# driver_and_mosfets.net
KiCad netlist of a schematic drawn in Altium Designer
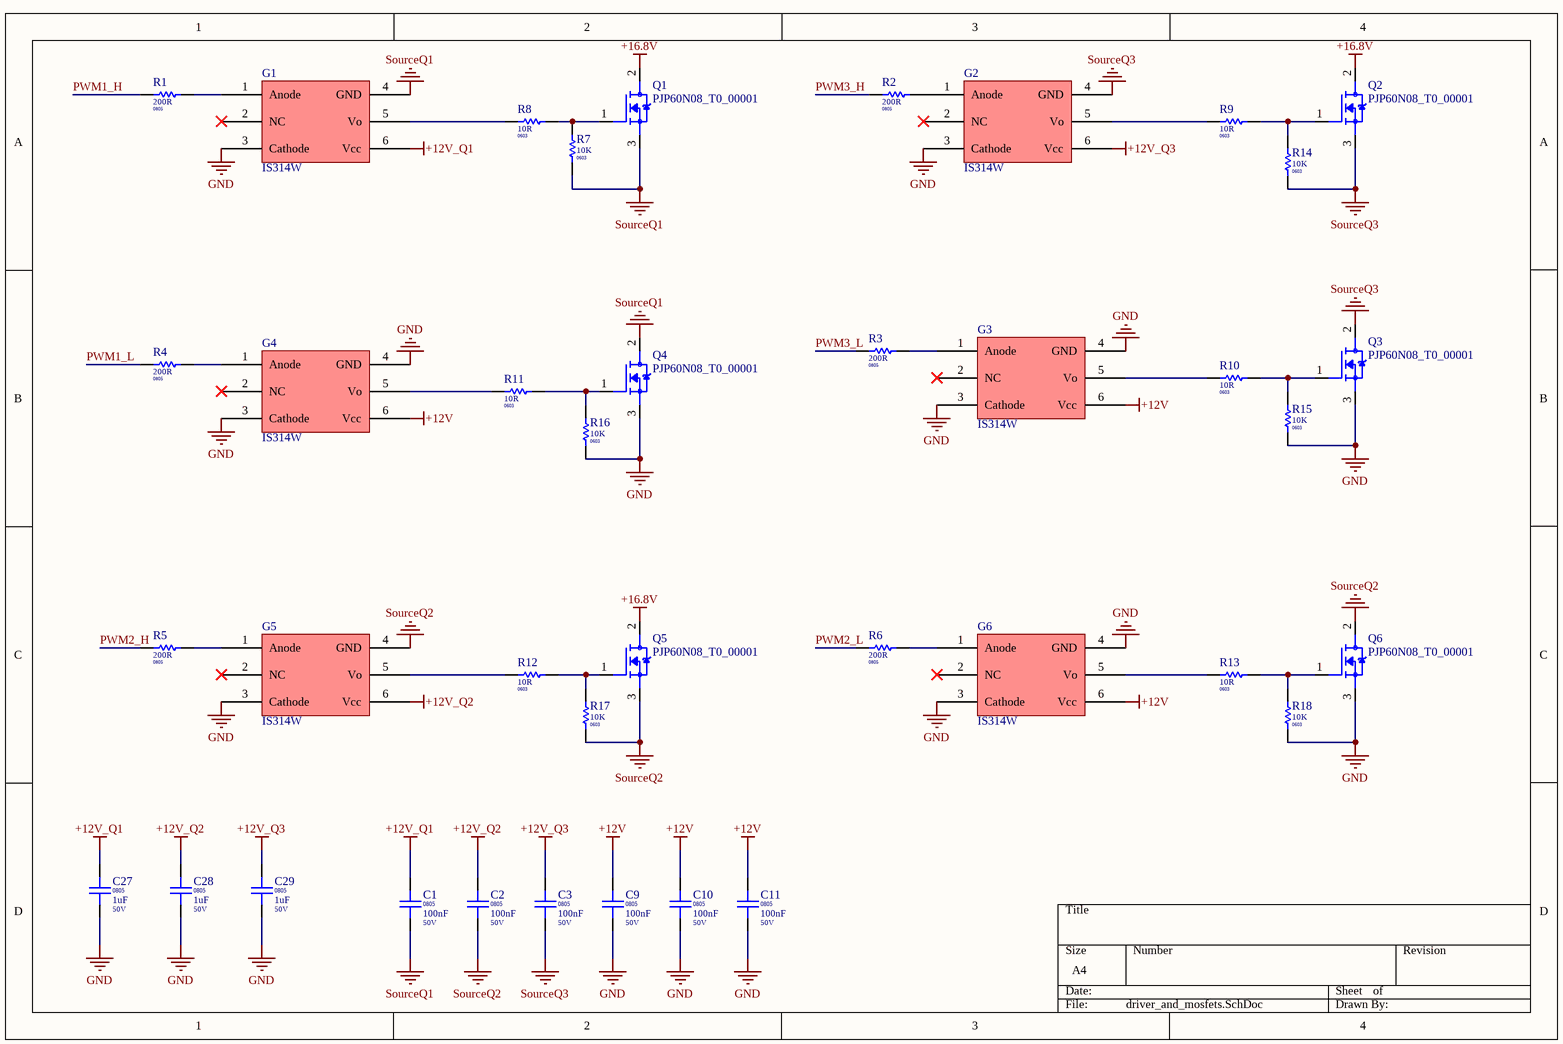
[diagram p0: driver_and_mosfets.SchDoc]

(export (version "E")
  (design (tool "Eeschema 10.0.6"))
  (components
    (comp (ref "C1")
      (value "100nF")
      (footprint "CAPC 0805")
      (description "Capacitor Ceramic 100nF 50V 0805")
      (fields
        (field (name "TOLERANCE") "%10")
        (field (name "PACKAGE / CASE") "0805")
        (field (name "VOLTAGE") "50V")
        (field (name "PART NUMBER") "CAPC0572")
      )
      (libsource (lib "AESK Database Library") (part "NPCapacitor"))
    )
    (comp (ref "C2")
      (value "100nF")
      (footprint "CAPC 0805")
      (description "Capacitor Ceramic 100nF 50V 0805")
      (fields
        (field (name "TOLERANCE") "%10")
        (field (name "PACKAGE / CASE") "0805")
        (field (name "VOLTAGE") "50V")
        (field (name "PART NUMBER") "CAPC0572")
      )
      (libsource (lib "AESK Database Library") (part "NPCapacitor"))
    )
    (comp (ref "C3")
      (value "100nF")
      (footprint "CAPC 0805")
      (description "Capacitor Ceramic 100nF 50V 0805")
      (fields
        (field (name "TOLERANCE") "%10")
        (field (name "PACKAGE / CASE") "0805")
        (field (name "VOLTAGE") "50V")
        (field (name "PART NUMBER") "CAPC0572")
      )
      (libsource (lib "AESK Database Library") (part "NPCapacitor"))
    )
    (comp (ref "C9")
      (value "100nF")
      (footprint "CAPC 0805")
      (description "Capacitor Ceramic 100nF 50V 0805")
      (fields
        (field (name "TOLERANCE") "%10")
        (field (name "PACKAGE / CASE") "0805")
        (field (name "VOLTAGE") "50V")
        (field (name "PART NUMBER") "CAPC0572")
      )
      (libsource (lib "AESK Database Library") (part "NPCapacitor"))
    )
    (comp (ref "C10")
      (value "100nF")
      (footprint "CAPC 0805")
      (description "Capacitor Ceramic 100nF 50V 0805")
      (fields
        (field (name "TOLERANCE") "%10")
        (field (name "PACKAGE / CASE") "0805")
        (field (name "VOLTAGE") "50V")
        (field (name "PART NUMBER") "CAPC0572")
      )
      (libsource (lib "AESK Database Library") (part "NPCapacitor"))
    )
    (comp (ref "C11")
      (value "100nF")
      (footprint "CAPC 0805")
      (description "Capacitor Ceramic 100nF 50V 0805")
      (fields
        (field (name "TOLERANCE") "%10")
        (field (name "PACKAGE / CASE") "0805")
        (field (name "VOLTAGE") "50V")
        (field (name "PART NUMBER") "CAPC0572")
      )
      (libsource (lib "AESK Database Library") (part "NPCapacitor"))
    )
    (comp (ref "C27")
      (value "1uF")
      (footprint "CAPC 0805")
      (description "Capacitor Ceramic 1uF 50V 0805")
      (fields
        (field (name "TOLERANCE") "%10")
        (field (name "PACKAGE / CASE") "0805")
        (field (name "VOLTAGE") "50V")
        (field (name "PART NUMBER") "CAPC0580")
      )
      (libsource (lib "AESK Database Library") (part "NPCapacitor"))
    )
    (comp (ref "C28")
      (value "1uF")
      (footprint "CAPC 0805")
      (description "Capacitor Ceramic 1uF 50V 0805")
      (fields
        (field (name "TOLERANCE") "%10")
        (field (name "PACKAGE / CASE") "0805")
        (field (name "VOLTAGE") "50V")
        (field (name "PART NUMBER") "CAPC0580")
      )
      (libsource (lib "AESK Database Library") (part "NPCapacitor"))
    )
    (comp (ref "C29")
      (value "1uF")
      (footprint "CAPC 0805")
      (description "Capacitor Ceramic 1uF 50V 0805")
      (fields
        (field (name "TOLERANCE") "%10")
        (field (name "PACKAGE / CASE") "0805")
        (field (name "VOLTAGE") "50V")
        (field (name "PART NUMBER") "CAPC0580")
      )
      (libsource (lib "AESK Database Library") (part "NPCapacitor"))
    )
    (comp (ref "G1")
      (value "IS314W")
      (footprint "SOIC127P1150X360-6N")
      (description "IC-314 OPTO GATE DRVR 5KV SO6 STRETCHED")
      (libsource (lib "ESC") (part "IS314W"))
    )
    (comp (ref "G2")
      (value "IS314W")
      (footprint "SOIC127P1150X360-6N")
      (description "IC-314 OPTO GATE DRVR 5KV SO6 STRETCHED")
      (libsource (lib "ESC") (part "IS314W"))
    )
    (comp (ref "G3")
      (value "IS314W")
      (footprint "SOIC127P1150X360-6N")
      (description "IC-314 OPTO GATE DRVR 5KV SO6 STRETCHED")
      (libsource (lib "ESC") (part "IS314W"))
    )
    (comp (ref "G4")
      (value "IS314W")
      (footprint "SOIC127P1150X360-6N")
      (description "IC-314 OPTO GATE DRVR 5KV SO6 STRETCHED")
      (libsource (lib "ESC") (part "IS314W"))
    )
    (comp (ref "G5")
      (value "IS314W")
      (footprint "SOIC127P1150X360-6N")
      (description "IC-314 OPTO GATE DRVR 5KV SO6 STRETCHED")
      (libsource (lib "ESC") (part "IS314W"))
    )
    (comp (ref "G6")
      (value "IS314W")
      (footprint "SOIC127P1150X360-6N")
      (description "IC-314 OPTO GATE DRVR 5KV SO6 STRETCHED")
      (libsource (lib "ESC") (part "IS314W"))
    )
    (comp (ref "Q1")
      (value "PJP60N08_T0_00001")
      (footprint "TO-220-3")
      (description "MOSFET DIS.60A 80V N-CH TO220AB SWITCH THT")
      (fields (field (name "MP") "IRF520NPBF") (field (name "MF") "Infineon Technologies"))
      (libsource (lib "ESC") (part "PJP60N08_T0_00001"))
    )
    (comp (ref "Q2")
      (value "PJP60N08_T0_00001")
      (footprint "TO-220-3")
      (description "MOSFET DIS.60A 80V N-CH TO220AB SWITCH THT")
      (fields (field (name "MP") "IRF520NPBF") (field (name "MF") "Infineon Technologies"))
      (libsource (lib "ESC") (part "PJP60N08_T0_00001"))
    )
    (comp (ref "Q3")
      (value "PJP60N08_T0_00001")
      (footprint "TO-220-3")
      (description "MOSFET DIS.60A 80V N-CH TO220AB SWITCH THT")
      (fields (field (name "MP") "IRF520NPBF") (field (name "MF") "Infineon Technologies"))
      (libsource (lib "ESC") (part "PJP60N08_T0_00001"))
    )
    (comp (ref "Q4")
      (value "PJP60N08_T0_00001")
      (footprint "TO-220-3")
      (description "MOSFET DIS.60A 80V N-CH TO220AB SWITCH THT")
      (fields (field (name "MP") "IRF520NPBF") (field (name "MF") "Infineon Technologies"))
      (libsource (lib "ESC") (part "PJP60N08_T0_00001"))
    )
    (comp (ref "Q5")
      (value "PJP60N08_T0_00001")
      (footprint "TO-220-3")
      (description "MOSFET DIS.60A 80V N-CH TO220AB SWITCH THT")
      (fields (field (name "MP") "IRF520NPBF") (field (name "MF") "Infineon Technologies"))
      (libsource (lib "ESC") (part "PJP60N08_T0_00001"))
    )
    (comp (ref "Q6")
      (value "PJP60N08_T0_00001")
      (footprint "TO-220-3")
      (description "MOSFET DIS.60A 80V N-CH TO220AB SWITCH THT")
      (fields (field (name "MP") "IRF520NPBF") (field (name "MF") "Infineon Technologies"))
      (libsource (lib "ESC") (part "PJP60N08_T0_00001"))
    )
    (comp (ref "R1")
      (value "200R")
      (footprint "RESC 0805")
      (description "200R 0805")
      (fields
        (field (name "TOLERANCE") "%5")
        (field (name "POWER") "1/10W")
        (field (name "PACKAGE / CASE") "0805")
      )
      (libsource (lib "AESK Database Library") (part "Resistor"))
    )
    (comp (ref "R2")
      (value "200R")
      (footprint "RESC 0805")
      (description "200R 0805")
      (fields
        (field (name "TOLERANCE") "%5")
        (field (name "POWER") "1/10W")
        (field (name "PACKAGE / CASE") "0805")
      )
      (libsource (lib "AESK Database Library") (part "Resistor"))
    )
    (comp (ref "R3")
      (value "200R")
      (footprint "RESC 0805")
      (description "200R 0805")
      (fields
        (field (name "TOLERANCE") "%5")
        (field (name "POWER") "1/10W")
        (field (name "PACKAGE / CASE") "0805")
      )
      (libsource (lib "AESK Database Library") (part "Resistor"))
    )
    (comp (ref "R4")
      (value "200R")
      (footprint "RESC 0805")
      (description "200R 0805")
      (fields
        (field (name "TOLERANCE") "%5")
        (field (name "POWER") "1/10W")
        (field (name "PACKAGE / CASE") "0805")
      )
      (libsource (lib "AESK Database Library") (part "Resistor"))
    )
    (comp (ref "R5")
      (value "200R")
      (footprint "RESC 0805")
      (description "200R 0805")
      (fields
        (field (name "TOLERANCE") "%5")
        (field (name "POWER") "1/10W")
        (field (name "PACKAGE / CASE") "0805")
      )
      (libsource (lib "AESK Database Library") (part "Resistor"))
    )
    (comp (ref "R6")
      (value "200R")
      (footprint "RESC 0805")
      (description "200R 0805")
      (fields
        (field (name "TOLERANCE") "%5")
        (field (name "POWER") "1/10W")
        (field (name "PACKAGE / CASE") "0805")
      )
      (libsource (lib "AESK Database Library") (part "Resistor"))
    )
    (comp (ref "R7")
      (value "10K")
      (footprint "RESC 0603")
      (description "10K 0603")
      (fields
        (field (name "TOLERANCE") "%5")
        (field (name "POWER") "1/10W")
        (field (name "PACKAGE / CASE") "0603")
      )
      (libsource (lib "AESK Database Library") (part "Resistor"))
    )
    (comp (ref "R8")
      (value "10R")
      (footprint "RESC 0603")
      (description "10R 0603")
      (fields
        (field (name "TOLERANCE") "%5")
        (field (name "POWER") "1/10W")
        (field (name "PACKAGE / CASE") "0603")
      )
      (libsource (lib "AESK Database Library") (part "Resistor"))
    )
    (comp (ref "R9")
      (value "10R")
      (footprint "RESC 0603")
      (description "10R 0603")
      (fields
        (field (name "TOLERANCE") "%5")
        (field (name "POWER") "1/10W")
        (field (name "PACKAGE / CASE") "0603")
      )
      (libsource (lib "AESK Database Library") (part "Resistor"))
    )
    (comp (ref "R10")
      (value "10R")
      (footprint "RESC 0603")
      (description "10R 0603")
      (fields
        (field (name "TOLERANCE") "%5")
        (field (name "POWER") "1/10W")
        (field (name "PACKAGE / CASE") "0603")
      )
      (libsource (lib "AESK Database Library") (part "Resistor"))
    )
    (comp (ref "R11")
      (value "10R")
      (footprint "RESC 0603")
      (description "10R 0603")
      (fields
        (field (name "TOLERANCE") "%5")
        (field (name "POWER") "1/10W")
        (field (name "PACKAGE / CASE") "0603")
      )
      (libsource (lib "AESK Database Library") (part "Resistor"))
    )
    (comp (ref "R12")
      (value "10R")
      (footprint "RESC 0603")
      (description "10R 0603")
      (fields
        (field (name "TOLERANCE") "%5")
        (field (name "POWER") "1/10W")
        (field (name "PACKAGE / CASE") "0603")
      )
      (libsource (lib "AESK Database Library") (part "Resistor"))
    )
    (comp (ref "R13")
      (value "10R")
      (footprint "RESC 0603")
      (description "10R 0603")
      (fields
        (field (name "TOLERANCE") "%5")
        (field (name "POWER") "1/10W")
        (field (name "PACKAGE / CASE") "0603")
      )
      (libsource (lib "AESK Database Library") (part "Resistor"))
    )
    (comp (ref "R14")
      (value "10K")
      (footprint "RESC 0603")
      (description "10K 0603")
      (fields
        (field (name "TOLERANCE") "%5")
        (field (name "POWER") "1/10W")
        (field (name "PACKAGE / CASE") "0603")
      )
      (libsource (lib "AESK Database Library") (part "Resistor"))
    )
    (comp (ref "R15")
      (value "10K")
      (footprint "RESC 0603")
      (description "10K 0603")
      (fields
        (field (name "TOLERANCE") "%5")
        (field (name "POWER") "1/10W")
        (field (name "PACKAGE / CASE") "0603")
      )
      (libsource (lib "AESK Database Library") (part "Resistor"))
    )
    (comp (ref "R16")
      (value "10K")
      (footprint "RESC 0603")
      (description "10K 0603")
      (fields
        (field (name "TOLERANCE") "%5")
        (field (name "POWER") "1/10W")
        (field (name "PACKAGE / CASE") "0603")
      )
      (libsource (lib "AESK Database Library") (part "Resistor"))
    )
    (comp (ref "R17")
      (value "10K")
      (footprint "RESC 0603")
      (description "10K 0603")
      (fields
        (field (name "TOLERANCE") "%5")
        (field (name "POWER") "1/10W")
        (field (name "PACKAGE / CASE") "0603")
      )
      (libsource (lib "AESK Database Library") (part "Resistor"))
    )
    (comp (ref "R18")
      (value "10K")
      (footprint "RESC 0603")
      (description "10K 0603")
      (fields
        (field (name "TOLERANCE") "%5")
        (field (name "POWER") "1/10W")
        (field (name "PACKAGE / CASE") "0603")
      )
      (libsource (lib "AESK Database Library") (part "Resistor"))
    )
  )
  (nets
    (net (code "1") (name "+12V") (class "Default")
      (node (ref "C10") (pin "2") (pinfunction "2_2") (pintype "passive"))
      (node (ref "C11") (pin "2") (pinfunction "2_2") (pintype "passive"))
      (node (ref "C9") (pin "2") (pinfunction "2_2") (pintype "passive"))
      (node (ref "G3") (pin "6") (pinfunction "Vcc_6") (pintype "passive"))
      (node (ref "G4") (pin "6") (pinfunction "Vcc_6") (pintype "passive"))
      (node (ref "G6") (pin "6") (pinfunction "Vcc_6") (pintype "passive"))
    )
    (net (code "2") (name "+12V_Q1") (class "Default")
      (node (ref "C1") (pin "2") (pinfunction "2_2") (pintype "passive"))
      (node (ref "C27") (pin "2") (pinfunction "2_2") (pintype "passive"))
      (node (ref "G1") (pin "6") (pinfunction "Vcc_6") (pintype "passive"))
    )
    (net (code "3") (name "+12V_Q2") (class "Default")
      (node (ref "C2") (pin "2") (pinfunction "2_2") (pintype "passive"))
      (node (ref "C28") (pin "2") (pinfunction "2_2") (pintype "passive"))
      (node (ref "G5") (pin "6") (pinfunction "Vcc_6") (pintype "passive"))
    )
    (net (code "4") (name "+12V_Q3") (class "Default")
      (node (ref "C29") (pin "2") (pinfunction "2_2") (pintype "passive"))
      (node (ref "C3") (pin "2") (pinfunction "2_2") (pintype "passive"))
      (node (ref "G2") (pin "6") (pinfunction "Vcc_6") (pintype "passive"))
    )
    (net (code "5") (name "+16.8V") (class "Default")
      (node (ref "Q1") (pin "2") (pinfunction "D_2") (pintype "passive"))
      (node (ref "Q2") (pin "2") (pinfunction "D_2") (pintype "passive"))
      (node (ref "Q5") (pin "2") (pinfunction "D_2") (pintype "passive"))
    )
    (net (code "6") (name "/PWM1_H") (class "Default")
      (node (ref "R1") (pin "1") (pinfunction "1_1") (pintype "passive"))
    )
    (net (code "7") (name "/PWM1_L") (class "Default")
      (node (ref "R4") (pin "1") (pinfunction "1_1") (pintype "passive"))
    )
    (net (code "8") (name "/PWM2_H") (class "Default")
      (node (ref "R5") (pin "1") (pinfunction "1_1") (pintype "passive"))
    )
    (net (code "9") (name "/PWM2_L") (class "Default")
      (node (ref "R6") (pin "1") (pinfunction "1_1") (pintype "passive"))
    )
    (net (code "10") (name "/PWM3_H") (class "Default")
      (node (ref "R2") (pin "1") (pinfunction "1_1") (pintype "passive"))
    )
    (net (code "11") (name "/PWM3_L") (class "Default")
      (node (ref "R3") (pin "1") (pinfunction "1_1") (pintype "passive"))
    )
    (net (code "12") (name "GND") (class "Default")
      (node (ref "C10") (pin "1") (pinfunction "1_1") (pintype "passive"))
      (node (ref "C11") (pin "1") (pinfunction "1_1") (pintype "passive"))
      (node (ref "C27") (pin "1") (pinfunction "1_1") (pintype "passive"))
      (node (ref "C28") (pin "1") (pinfunction "1_1") (pintype "passive"))
      (node (ref "C29") (pin "1") (pinfunction "1_1") (pintype "passive"))
      (node (ref "C9") (pin "1") (pinfunction "1_1") (pintype "passive"))
      (node (ref "G1") (pin "3") (pinfunction "Cathode_3") (pintype "passive"))
      (node (ref "G2") (pin "3") (pinfunction "Cathode_3") (pintype "passive"))
      (node (ref "G3") (pin "3") (pinfunction "Cathode_3") (pintype "passive"))
      (node (ref "G3") (pin "4") (pinfunction "GND_4") (pintype "passive"))
      (node (ref "G4") (pin "3") (pinfunction "Cathode_3") (pintype "passive"))
      (node (ref "G4") (pin "4") (pinfunction "GND_4") (pintype "passive"))
      (node (ref "G5") (pin "3") (pinfunction "Cathode_3") (pintype "passive"))
      (node (ref "G6") (pin "3") (pinfunction "Cathode_3") (pintype "passive"))
      (node (ref "G6") (pin "4") (pinfunction "GND_4") (pintype "passive"))
      (node (ref "Q3") (pin "3") (pinfunction "S_3") (pintype "passive"))
      (node (ref "Q4") (pin "3") (pinfunction "S_3") (pintype "passive"))
      (node (ref "Q6") (pin "3") (pinfunction "S_3") (pintype "passive"))
      (node (ref "R15") (pin "1") (pinfunction "1_1") (pintype "passive"))
      (node (ref "R16") (pin "1") (pinfunction "1_1") (pintype "passive"))
      (node (ref "R18") (pin "1") (pinfunction "1_1") (pintype "passive"))
    )
    (net (code "13") (name "Net-(G1-Anode)") (class "Default")
      (node (ref "G1") (pin "1") (pinfunction "Anode_1") (pintype "passive"))
      (node (ref "R1") (pin "2") (pinfunction "2_2") (pintype "passive"))
    )
    (net (code "14") (name "Net-(G1-Vo)") (class "Default")
      (node (ref "G1") (pin "5") (pinfunction "Vo_5") (pintype "passive"))
      (node (ref "R8") (pin "1") (pinfunction "1_1") (pintype "passive"))
    )
    (net (code "15") (name "Net-(G2-Anode)") (class "Default")
      (node (ref "G2") (pin "1") (pinfunction "Anode_1") (pintype "passive"))
      (node (ref "R2") (pin "2") (pinfunction "2_2") (pintype "passive"))
    )
    (net (code "16") (name "Net-(G2-Vo)") (class "Default")
      (node (ref "G2") (pin "5") (pinfunction "Vo_5") (pintype "passive"))
      (node (ref "R9") (pin "1") (pinfunction "1_1") (pintype "passive"))
    )
    (net (code "17") (name "Net-(G3-Anode)") (class "Default")
      (node (ref "G3") (pin "1") (pinfunction "Anode_1") (pintype "passive"))
      (node (ref "R3") (pin "2") (pinfunction "2_2") (pintype "passive"))
    )
    (net (code "18") (name "Net-(G3-Vo)") (class "Default")
      (node (ref "G3") (pin "5") (pinfunction "Vo_5") (pintype "passive"))
      (node (ref "R10") (pin "1") (pinfunction "1_1") (pintype "passive"))
    )
    (net (code "19") (name "Net-(G4-Anode)") (class "Default")
      (node (ref "G4") (pin "1") (pinfunction "Anode_1") (pintype "passive"))
      (node (ref "R4") (pin "2") (pinfunction "2_2") (pintype "passive"))
    )
    (net (code "20") (name "Net-(G4-Vo)") (class "Default")
      (node (ref "G4") (pin "5") (pinfunction "Vo_5") (pintype "passive"))
      (node (ref "R11") (pin "1") (pinfunction "1_1") (pintype "passive"))
    )
    (net (code "21") (name "Net-(G5-Anode)") (class "Default")
      (node (ref "G5") (pin "1") (pinfunction "Anode_1") (pintype "passive"))
      (node (ref "R5") (pin "2") (pinfunction "2_2") (pintype "passive"))
    )
    (net (code "22") (name "Net-(G5-Vo)") (class "Default")
      (node (ref "G5") (pin "5") (pinfunction "Vo_5") (pintype "passive"))
      (node (ref "R12") (pin "1") (pinfunction "1_1") (pintype "passive"))
    )
    (net (code "23") (name "Net-(G6-Anode)") (class "Default")
      (node (ref "G6") (pin "1") (pinfunction "Anode_1") (pintype "passive"))
      (node (ref "R6") (pin "2") (pinfunction "2_2") (pintype "passive"))
    )
    (net (code "24") (name "Net-(G6-Vo)") (class "Default")
      (node (ref "G6") (pin "5") (pinfunction "Vo_5") (pintype "passive"))
      (node (ref "R13") (pin "1") (pinfunction "1_1") (pintype "passive"))
    )
    (net (code "25") (name "Net-(Q1-G)") (class "Default")
      (node (ref "Q1") (pin "1") (pinfunction "G_1") (pintype "passive"))
      (node (ref "R7") (pin "2") (pinfunction "2_2") (pintype "passive"))
      (node (ref "R8") (pin "2") (pinfunction "2_2") (pintype "passive"))
    )
    (net (code "26") (name "Net-(Q2-G)") (class "Default")
      (node (ref "Q2") (pin "1") (pinfunction "G_1") (pintype "passive"))
      (node (ref "R14") (pin "2") (pinfunction "2_2") (pintype "passive"))
      (node (ref "R9") (pin "2") (pinfunction "2_2") (pintype "passive"))
    )
    (net (code "27") (name "Net-(Q3-G)") (class "Default")
      (node (ref "Q3") (pin "1") (pinfunction "G_1") (pintype "passive"))
      (node (ref "R10") (pin "2") (pinfunction "2_2") (pintype "passive"))
      (node (ref "R15") (pin "2") (pinfunction "2_2") (pintype "passive"))
    )
    (net (code "28") (name "Net-(Q4-G)") (class "Default")
      (node (ref "Q4") (pin "1") (pinfunction "G_1") (pintype "passive"))
      (node (ref "R11") (pin "2") (pinfunction "2_2") (pintype "passive"))
      (node (ref "R16") (pin "2") (pinfunction "2_2") (pintype "passive"))
    )
    (net (code "29") (name "Net-(Q5-G)") (class "Default")
      (node (ref "Q5") (pin "1") (pinfunction "G_1") (pintype "passive"))
      (node (ref "R12") (pin "2") (pinfunction "2_2") (pintype "passive"))
      (node (ref "R17") (pin "2") (pinfunction "2_2") (pintype "passive"))
    )
    (net (code "30") (name "Net-(Q6-G)") (class "Default")
      (node (ref "Q6") (pin "1") (pinfunction "G_1") (pintype "passive"))
      (node (ref "R13") (pin "2") (pinfunction "2_2") (pintype "passive"))
      (node (ref "R18") (pin "2") (pinfunction "2_2") (pintype "passive"))
    )
    (net (code "31") (name "SourceQ1") (class "Default")
      (node (ref "C1") (pin "1") (pinfunction "1_1") (pintype "passive"))
      (node (ref "G1") (pin "4") (pinfunction "GND_4") (pintype "passive"))
      (node (ref "Q1") (pin "3") (pinfunction "S_3") (pintype "passive"))
      (node (ref "Q4") (pin "2") (pinfunction "D_2") (pintype "passive"))
      (node (ref "R7") (pin "1") (pinfunction "1_1") (pintype "passive"))
    )
    (net (code "32") (name "SourceQ2") (class "Default")
      (node (ref "C2") (pin "1") (pinfunction "1_1") (pintype "passive"))
      (node (ref "G5") (pin "4") (pinfunction "GND_4") (pintype "passive"))
      (node (ref "Q5") (pin "3") (pinfunction "S_3") (pintype "passive"))
      (node (ref "Q6") (pin "2") (pinfunction "D_2") (pintype "passive"))
      (node (ref "R17") (pin "1") (pinfunction "1_1") (pintype "passive"))
    )
    (net (code "33") (name "SourceQ3") (class "Default")
      (node (ref "C3") (pin "1") (pinfunction "1_1") (pintype "passive"))
      (node (ref "G2") (pin "4") (pinfunction "GND_4") (pintype "passive"))
      (node (ref "Q2") (pin "3") (pinfunction "S_3") (pintype "passive"))
      (node (ref "Q3") (pin "2") (pinfunction "D_2") (pintype "passive"))
      (node (ref "R14") (pin "1") (pinfunction "1_1") (pintype "passive"))
    )
    (net (code "34") (name "unconnected-(G1-NC-Pad2)") (class "Default")
      (node (ref "G1") (pin "2") (pinfunction "NC_2") (pintype "passive+no_connect"))
    )
    (net (code "35") (name "unconnected-(G2-NC-Pad2)") (class "Default")
      (node (ref "G2") (pin "2") (pinfunction "NC_2") (pintype "passive+no_connect"))
    )
    (net (code "36") (name "unconnected-(G3-NC-Pad2)") (class "Default")
      (node (ref "G3") (pin "2") (pinfunction "NC_2") (pintype "passive+no_connect"))
    )
    (net (code "37") (name "unconnected-(G4-NC-Pad2)") (class "Default")
      (node (ref "G4") (pin "2") (pinfunction "NC_2") (pintype "passive+no_connect"))
    )
    (net (code "38") (name "unconnected-(G5-NC-Pad2)") (class "Default")
      (node (ref "G5") (pin "2") (pinfunction "NC_2") (pintype "passive+no_connect"))
    )
    (net (code "39") (name "unconnected-(G6-NC-Pad2)") (class "Default")
      (node (ref "G6") (pin "2") (pinfunction "NC_2") (pintype "passive+no_connect"))
    )
  )
)
